# design.net
KiCad netlist of a schematic drawn in EasyEDA Pro
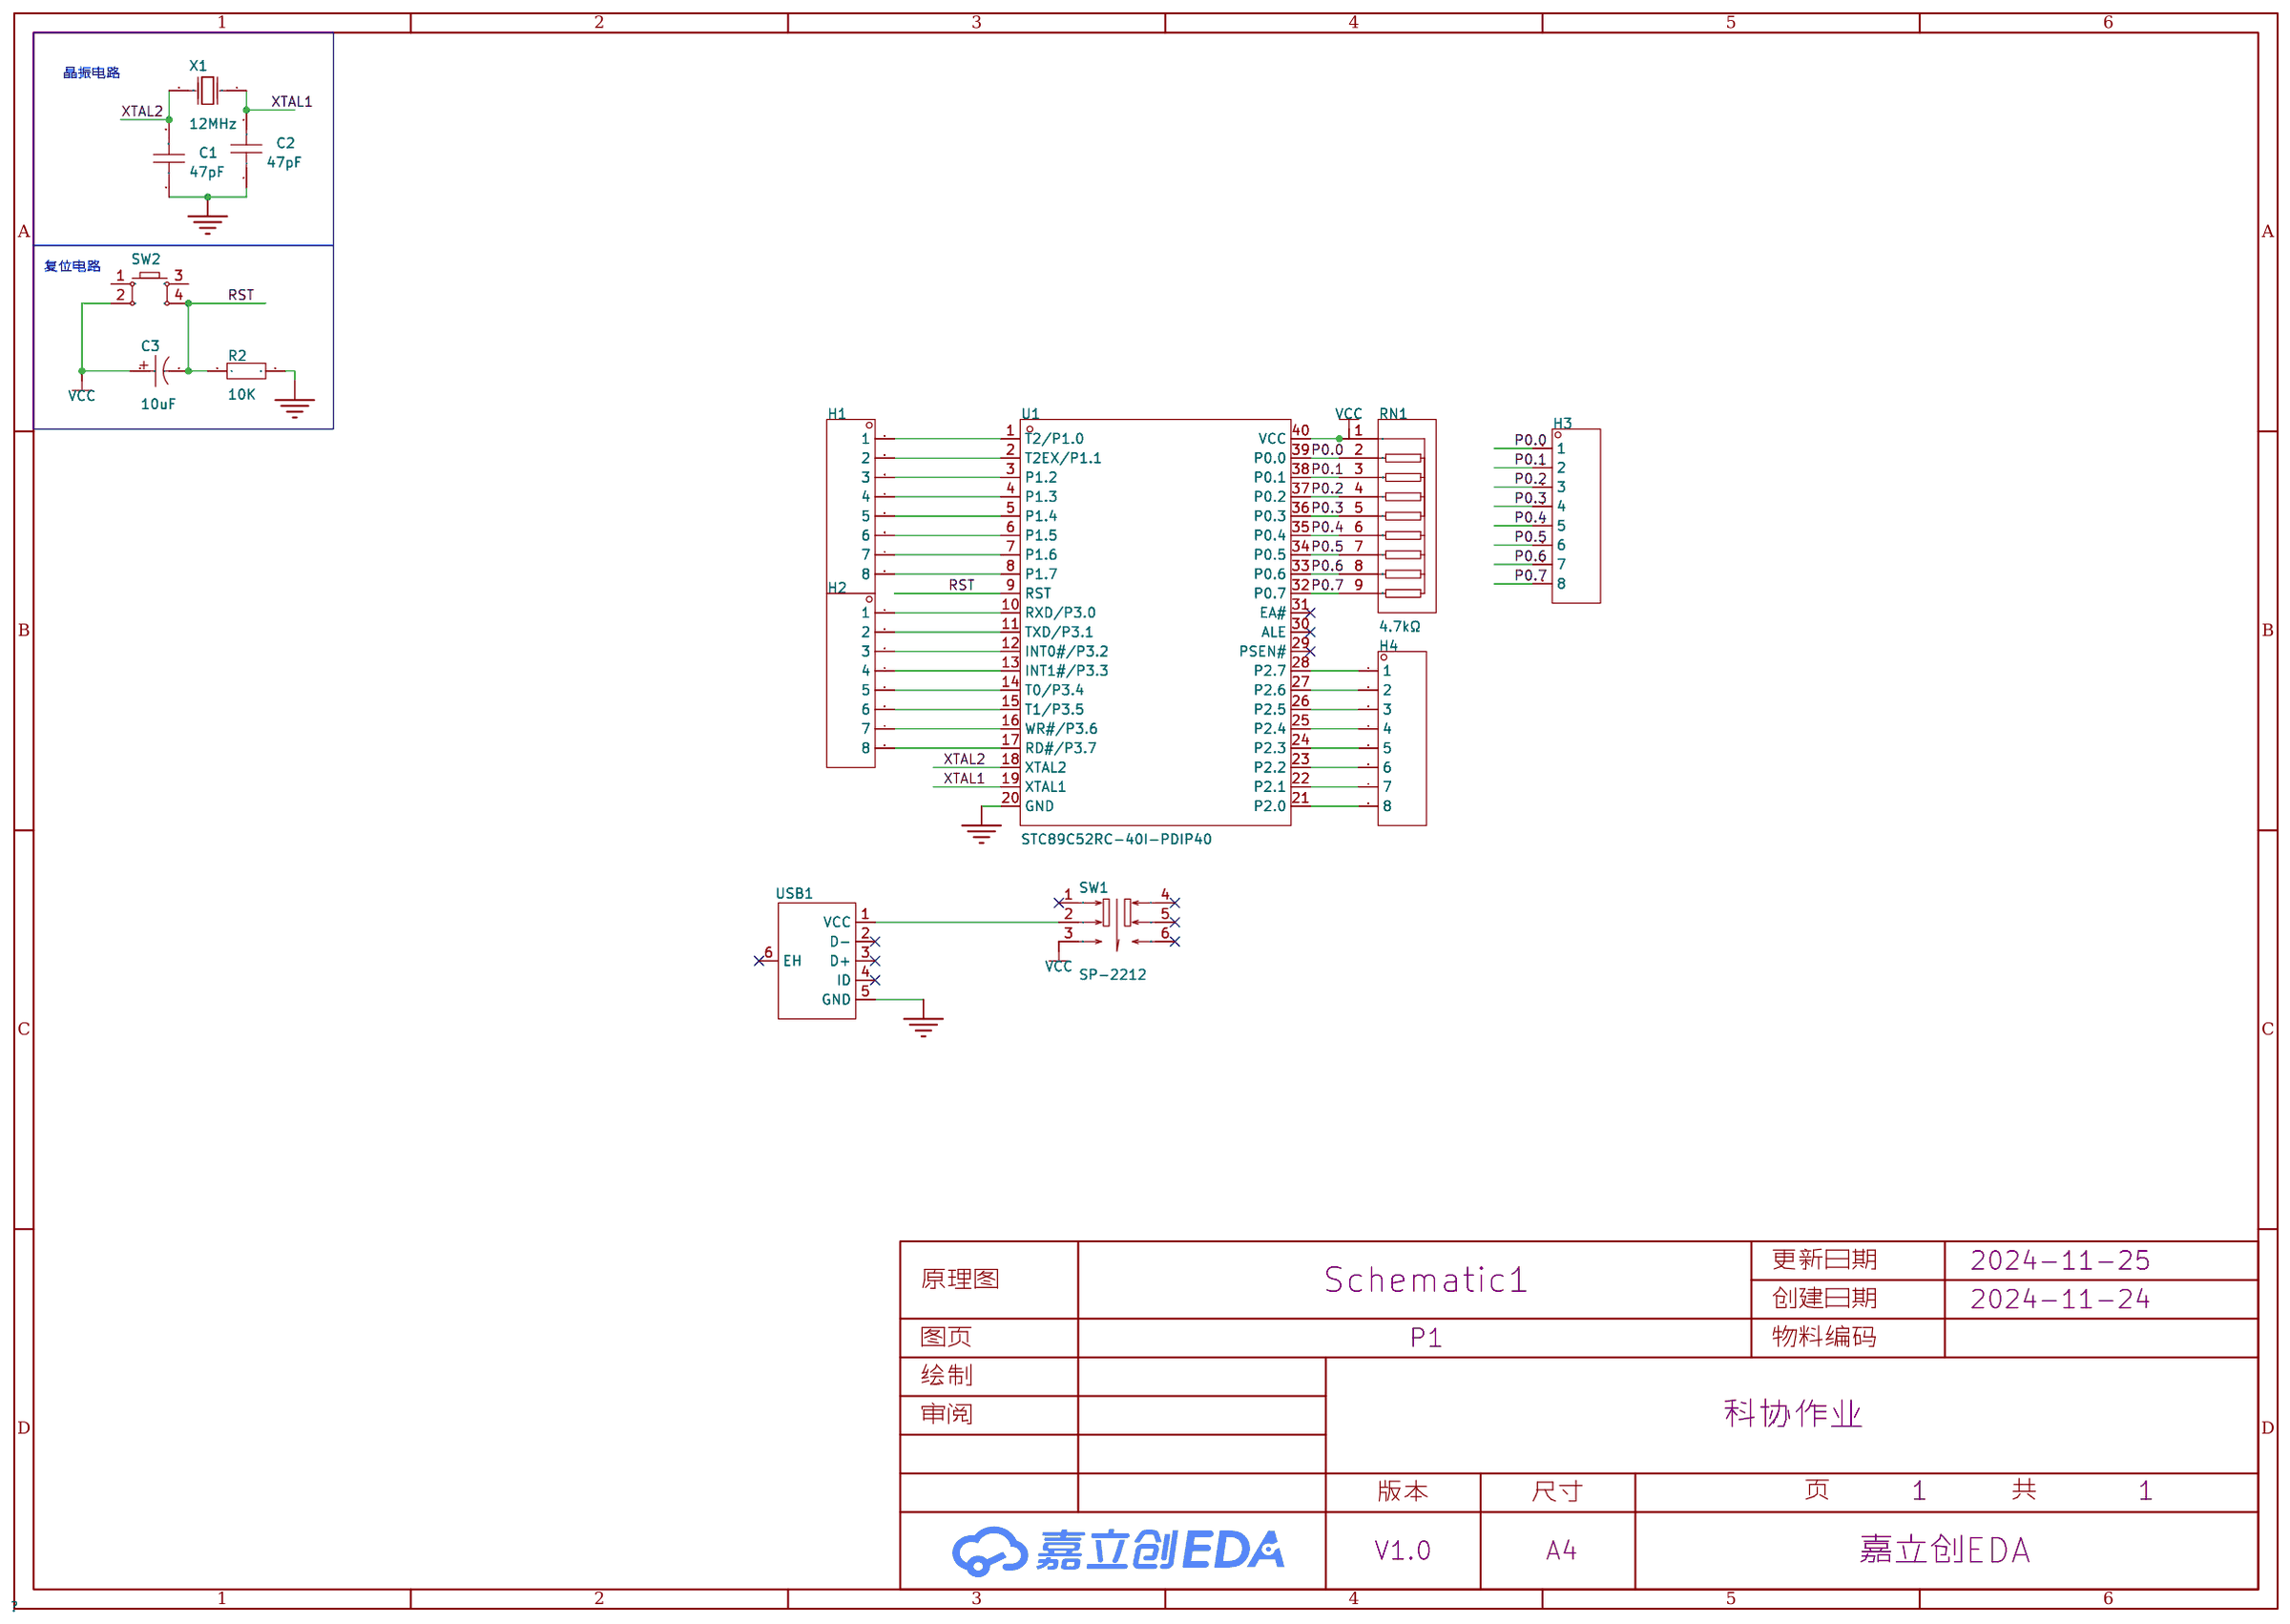
[diagram p0: schematic sheet]

(export (version "E")
  (design (tool "Eeschema 10.0.6"))
  (components
    (comp (ref "C1")
      (value "47pF")
      (footprint "easyedapro:C0603")
      (libsource (lib "easyedapro") (part "CapAcitance"))
    )
    (comp (ref "C2")
      (value "47pF")
      (footprint "easyedapro:C0603")
      (libsource (lib "easyedapro") (part "CapAcitance"))
    )
    (comp (ref "C3")
      (value "10uF")
      (footprint "easyedapro:CAP-TH_BD10.0-P5.00-D1.0-FD")
      (description "容值:220uF;精度:±20%;额定电压:50V;")
      (fields (field (name "Manufacturer Part") "ERS1HM221G16OT") (field (name "Manufacturer") "AISHI(艾华集团)"))
      (libsource (lib "easyedapro") (part "ERS1HM221G16OT"))
    )
    (comp (ref "H1")
      (value "~")
      (footprint "easyedapro:HDR-TH_8P-P2.54-V-M")
      (libsource (lib "easyedapro") (part "Header-Male-2.54_1x8"))
    )
    (comp (ref "H2")
      (value "~")
      (footprint "easyedapro:HDR-TH_8P-P2.54-V-M")
      (libsource (lib "easyedapro") (part "Header-Male-2.54_1x8"))
    )
    (comp (ref "H3")
      (value "~")
      (footprint "easyedapro:HDR-TH_8P-P2.54-V-M")
      (libsource (lib "easyedapro") (part "Header-Male-2.54_1x8"))
    )
    (comp (ref "H4")
      (value "~")
      (footprint "easyedapro:HDR-TH_8P-P2.54-V-M")
      (libsource (lib "easyedapro") (part "Header-Male-2.54_1x8"))
    )
    (comp (ref "R2") (value "10K") (footprint "easyedapro:R2010") (libsource (lib "easyedapro") (part "电阻")))
    (comp (ref "RN1")
      (value "4.7kΩ")
      (footprint "easyedapro:RES-ARRAY-TH_9P-P2.54-D1.0")
      (description "电阻器数:8;阻值:4.7kΩ;精度:±5%;单个元件功率:125mW;温度系数:±100ppm/°C;")
      (fields (field (name "Manufacturer Part") "A09-472JP") (field (name "Manufacturer") "FH(风华)"))
      (libsource (lib "easyedapro") (part "A09-472JP"))
    )
    (comp (ref "SW1")
      (value "SP-2212")
      (footprint "easyedapro:SW-TH_6P-L7.2-W7.2-P2.00-LS5.0")
      (description "电路结构:双刀双掷;自锁/无锁:自锁;安装方式:直插;触点电流:100mA;额定电压 (DC):30V;作用力:230gf;机械寿命:1.2万次;")
      (fields (field (name "Manufacturer") "RISHENG(日昇)"))
      (libsource (lib "easyedapro") (part "SP-2212"))
    )
    (comp (ref "SW2")
      (value "~")
      (footprint "easyedapro:Key_SMD_12x12x7.3")
      (libsource (lib "easyedapro") (part "轻触按键"))
    )
    (comp (ref "U1")
      (value "STC89C52RC-40I-PDIP40")
      (footprint "easyedapro:DIP-40_L52.0-W13.7-P2.54-LS15.2-BL")
      (description "CPU内核:51系列;程序存储容量:8KB;RAM总容量:512Byte;GPIO端口数量:35;工作电压范围:3.3V~5.5V;CPU最大主频:-;程序存储器类型:FLASH;")
      (fields (field (name "Manufacturer") "STC(宏晶)"))
      (libsource (lib "easyedapro") (part "STC89C52RC-40I"))
    )
    (comp (ref "USB1")
      (value "~")
      (footprint "easyedapro:USB_Micro")
      (libsource (lib "easyedapro") (part "USB_Micro"))
    )
    (comp (ref "X1")
      (value "12MHz")
      (footprint "easyedapro:HC-49US_L11.5-W4.5-P4.88")
      (description "晶振类型:直插晶振;频率:13MHz;常温频差:±20ppm;外接负载电容:20pF;频率稳定度(全温):±30ppm;")
      (fields (field (name "Manufacturer Part") "X49SD13MSD2SC") (field (name "Manufacturer") "YXC(扬兴晶振)"))
      (libsource (lib "easyedapro") (part "X49SD13MSD2SC"))
    )
  )
  (nets
    (net (code "1") (name "/P0.0") (class "Default")
      (node (ref "H3") (pin "1") (pinfunction "1_1") (pintype "unspecified"))
      (node (ref "RN1") (pin "2") (pinfunction "2_2") (pintype "unspecified"))
      (node (ref "U1") (pin "39") (pinfunction "P0.0_39") (pintype "unspecified"))
    )
    (net (code "2") (name "/P0.1") (class "Default")
      (node (ref "H3") (pin "2") (pinfunction "2_2") (pintype "unspecified"))
      (node (ref "RN1") (pin "3") (pinfunction "3_3") (pintype "unspecified"))
      (node (ref "U1") (pin "38") (pinfunction "P0.1_38") (pintype "unspecified"))
    )
    (net (code "3") (name "/P0.2") (class "Default")
      (node (ref "H3") (pin "3") (pinfunction "3_3") (pintype "unspecified"))
      (node (ref "RN1") (pin "4") (pinfunction "4_4") (pintype "unspecified"))
      (node (ref "U1") (pin "37") (pinfunction "P0.2_37") (pintype "unspecified"))
    )
    (net (code "4") (name "/P0.3") (class "Default")
      (node (ref "H3") (pin "4") (pinfunction "4_4") (pintype "unspecified"))
      (node (ref "RN1") (pin "5") (pinfunction "5_5") (pintype "unspecified"))
      (node (ref "U1") (pin "36") (pinfunction "P0.3_36") (pintype "unspecified"))
    )
    (net (code "5") (name "/P0.4") (class "Default")
      (node (ref "H3") (pin "5") (pinfunction "5_5") (pintype "unspecified"))
      (node (ref "RN1") (pin "6") (pinfunction "6_6") (pintype "unspecified"))
      (node (ref "U1") (pin "35") (pinfunction "P0.4_35") (pintype "unspecified"))
    )
    (net (code "6") (name "/P0.5") (class "Default")
      (node (ref "H3") (pin "6") (pinfunction "6_6") (pintype "unspecified"))
      (node (ref "RN1") (pin "7") (pinfunction "7_7") (pintype "unspecified"))
      (node (ref "U1") (pin "34") (pinfunction "P0.5_34") (pintype "unspecified"))
    )
    (net (code "7") (name "/P0.6") (class "Default")
      (node (ref "H3") (pin "7") (pinfunction "7_7") (pintype "unspecified"))
      (node (ref "RN1") (pin "8") (pinfunction "8_8") (pintype "unspecified"))
      (node (ref "U1") (pin "33") (pinfunction "P0.6_33") (pintype "unspecified"))
    )
    (net (code "8") (name "/P0.7") (class "Default")
      (node (ref "H3") (pin "8") (pinfunction "8_8") (pintype "unspecified"))
      (node (ref "RN1") (pin "9") (pinfunction "9_9") (pintype "unspecified"))
      (node (ref "U1") (pin "32") (pinfunction "P0.7_32") (pintype "unspecified"))
    )
    (net (code "9") (name "/RST") (class "Default")
      (node (ref "C3") (pin "2") (pinfunction "2_2") (pintype "input"))
      (node (ref "R2") (pin "1") (pinfunction "1_1") (pintype "input"))
      (node (ref "SW2") (pin "4") (pinfunction "4_4") (pintype "input"))
      (node (ref "U1") (pin "9") (pinfunction "RST_9") (pintype "unspecified"))
    )
    (net (code "10") (name "/XTAL1") (class "Default")
      (node (ref "C2") (pin "2") (pinfunction "2_2") (pintype "input"))
      (node (ref "U1") (pin "19") (pinfunction "XTAL1_19") (pintype "unspecified"))
      (node (ref "X1") (pin "1") (pinfunction "OSC1_1") (pintype "input"))
    )
    (net (code "11") (name "/XTAL2") (class "Default")
      (node (ref "C1") (pin "2") (pinfunction "2_2") (pintype "input"))
      (node (ref "U1") (pin "18") (pinfunction "XTAL2_18") (pintype "unspecified"))
      (node (ref "X1") (pin "2") (pinfunction "OSC2_2") (pintype "input"))
    )
    (net (code "12") (name "GND") (class "Default")
      (node (ref "C1") (pin "1") (pinfunction "1_1") (pintype "input"))
      (node (ref "C2") (pin "1") (pinfunction "1_1") (pintype "input"))
      (node (ref "R2") (pin "2") (pinfunction "2_2") (pintype "input"))
      (node (ref "U1") (pin "20") (pinfunction "GND_20") (pintype "unspecified"))
      (node (ref "USB1") (pin "5") (pinfunction "GND_5") (pintype "input"))
    )
    (net (code "13") (name "Net-(U1-INT0#{slash}P3.2)") (class "Default")
      (node (ref "H2") (pin "3") (pinfunction "3_3") (pintype "unspecified"))
      (node (ref "U1") (pin "12") (pinfunction "INT0#/P3.2_12") (pintype "unspecified"))
    )
    (net (code "14") (name "Net-(U1-INT1#{slash}P3.3)") (class "Default")
      (node (ref "H2") (pin "4") (pinfunction "4_4") (pintype "unspecified"))
      (node (ref "U1") (pin "13") (pinfunction "INT1#/P3.3_13") (pintype "unspecified"))
    )
    (net (code "15") (name "Net-(U1-P1.2)") (class "Default")
      (node (ref "H1") (pin "3") (pinfunction "3_3") (pintype "unspecified"))
      (node (ref "U1") (pin "3") (pinfunction "P1.2_3") (pintype "unspecified"))
    )
    (net (code "16") (name "Net-(U1-P1.3)") (class "Default")
      (node (ref "H1") (pin "4") (pinfunction "4_4") (pintype "unspecified"))
      (node (ref "U1") (pin "4") (pinfunction "P1.3_4") (pintype "unspecified"))
    )
    (net (code "17") (name "Net-(U1-P1.4)") (class "Default")
      (node (ref "H1") (pin "5") (pinfunction "5_5") (pintype "unspecified"))
      (node (ref "U1") (pin "5") (pinfunction "P1.4_5") (pintype "unspecified"))
    )
    (net (code "18") (name "Net-(U1-P1.5)") (class "Default")
      (node (ref "H1") (pin "6") (pinfunction "6_6") (pintype "unspecified"))
      (node (ref "U1") (pin "6") (pinfunction "P1.5_6") (pintype "unspecified"))
    )
    (net (code "19") (name "Net-(U1-P1.6)") (class "Default")
      (node (ref "H1") (pin "7") (pinfunction "7_7") (pintype "unspecified"))
      (node (ref "U1") (pin "7") (pinfunction "P1.6_7") (pintype "unspecified"))
    )
    (net (code "20") (name "Net-(U1-P1.7)") (class "Default")
      (node (ref "H1") (pin "8") (pinfunction "8_8") (pintype "unspecified"))
      (node (ref "U1") (pin "8") (pinfunction "P1.7_8") (pintype "unspecified"))
    )
    (net (code "21") (name "Net-(U1-P2.0)") (class "Default")
      (node (ref "H4") (pin "8") (pinfunction "8_8") (pintype "unspecified"))
      (node (ref "U1") (pin "21") (pinfunction "P2.0_21") (pintype "unspecified"))
    )
    (net (code "22") (name "Net-(U1-P2.1)") (class "Default")
      (node (ref "H4") (pin "7") (pinfunction "7_7") (pintype "unspecified"))
      (node (ref "U1") (pin "22") (pinfunction "P2.1_22") (pintype "unspecified"))
    )
    (net (code "23") (name "Net-(U1-P2.2)") (class "Default")
      (node (ref "H4") (pin "6") (pinfunction "6_6") (pintype "unspecified"))
      (node (ref "U1") (pin "23") (pinfunction "P2.2_23") (pintype "unspecified"))
    )
    (net (code "24") (name "Net-(U1-P2.3)") (class "Default")
      (node (ref "H4") (pin "5") (pinfunction "5_5") (pintype "unspecified"))
      (node (ref "U1") (pin "24") (pinfunction "P2.3_24") (pintype "unspecified"))
    )
    (net (code "25") (name "Net-(U1-P2.4)") (class "Default")
      (node (ref "H4") (pin "4") (pinfunction "4_4") (pintype "unspecified"))
      (node (ref "U1") (pin "25") (pinfunction "P2.4_25") (pintype "unspecified"))
    )
    (net (code "26") (name "Net-(U1-P2.5)") (class "Default")
      (node (ref "H4") (pin "3") (pinfunction "3_3") (pintype "unspecified"))
      (node (ref "U1") (pin "26") (pinfunction "P2.5_26") (pintype "unspecified"))
    )
    (net (code "27") (name "Net-(U1-P2.6)") (class "Default")
      (node (ref "H4") (pin "2") (pinfunction "2_2") (pintype "unspecified"))
      (node (ref "U1") (pin "27") (pinfunction "P2.6_27") (pintype "unspecified"))
    )
    (net (code "28") (name "Net-(U1-P2.7)") (class "Default")
      (node (ref "H4") (pin "1") (pinfunction "1_1") (pintype "unspecified"))
      (node (ref "U1") (pin "28") (pinfunction "P2.7_28") (pintype "unspecified"))
    )
    (net (code "29") (name "Net-(U1-RD#{slash}P3.7)") (class "Default")
      (node (ref "H2") (pin "8") (pinfunction "8_8") (pintype "unspecified"))
      (node (ref "U1") (pin "17") (pinfunction "RD#/P3.7_17") (pintype "unspecified"))
    )
    (net (code "30") (name "Net-(U1-RXD{slash}P3.0)") (class "Default")
      (node (ref "H2") (pin "1") (pinfunction "1_1") (pintype "unspecified"))
      (node (ref "U1") (pin "10") (pinfunction "RXD/P3.0_10") (pintype "unspecified"))
    )
    (net (code "31") (name "Net-(U1-T0{slash}P3.4)") (class "Default")
      (node (ref "H2") (pin "5") (pinfunction "5_5") (pintype "unspecified"))
      (node (ref "U1") (pin "14") (pinfunction "T0/P3.4_14") (pintype "unspecified"))
    )
    (net (code "32") (name "Net-(U1-T1{slash}P3.5)") (class "Default")
      (node (ref "H2") (pin "6") (pinfunction "6_6") (pintype "unspecified"))
      (node (ref "U1") (pin "15") (pinfunction "T1/P3.5_15") (pintype "unspecified"))
    )
    (net (code "33") (name "Net-(U1-T2EX{slash}P1.1)") (class "Default")
      (node (ref "H1") (pin "2") (pinfunction "2_2") (pintype "unspecified"))
      (node (ref "U1") (pin "2") (pinfunction "T2EX/P1.1_2") (pintype "unspecified"))
    )
    (net (code "34") (name "Net-(U1-T2{slash}P1.0)") (class "Default")
      (node (ref "H1") (pin "1") (pinfunction "1_1") (pintype "unspecified"))
      (node (ref "U1") (pin "1") (pinfunction "T2/P1.0_1") (pintype "unspecified"))
    )
    (net (code "35") (name "Net-(U1-TXD{slash}P3.1)") (class "Default")
      (node (ref "H2") (pin "2") (pinfunction "2_2") (pintype "unspecified"))
      (node (ref "U1") (pin "11") (pinfunction "TXD/P3.1_11") (pintype "unspecified"))
    )
    (net (code "36") (name "Net-(U1-WR#{slash}P3.6)") (class "Default")
      (node (ref "H2") (pin "7") (pinfunction "7_7") (pintype "unspecified"))
      (node (ref "U1") (pin "16") (pinfunction "WR#/P3.6_16") (pintype "unspecified"))
    )
    (net (code "37") (name "Net-(USB1-VCC)") (class "Default")
      (node (ref "SW1") (pin "2") (pinfunction "2_2") (pintype "unspecified"))
      (node (ref "USB1") (pin "1") (pinfunction "VCC_1") (pintype "input"))
    )
    (net (code "38") (name "VCC") (class "Default")
      (node (ref "C3") (pin "1") (pinfunction "1_1") (pintype "input"))
      (node (ref "RN1") (pin "1") (pinfunction "1_1") (pintype "unspecified"))
      (node (ref "SW1") (pin "3") (pinfunction "3_3") (pintype "unspecified"))
      (node (ref "SW2") (pin "2") (pinfunction "2_2") (pintype "input"))
      (node (ref "U1") (pin "40") (pinfunction "VCC_40") (pintype "unspecified"))
    )
    (net (code "39") (name "unconnected-(SW1-Pad1)") (class "Default")
      (node (ref "SW1") (pin "1") (pinfunction "1_1") (pintype "unspecified+no_connect"))
    )
    (net (code "40") (name "unconnected-(SW1-Pad4)") (class "Default")
      (node (ref "SW1") (pin "4") (pinfunction "4_4") (pintype "unspecified+no_connect"))
    )
    (net (code "41") (name "unconnected-(SW1-Pad5)") (class "Default")
      (node (ref "SW1") (pin "5") (pinfunction "5_5") (pintype "unspecified+no_connect"))
    )
    (net (code "42") (name "unconnected-(SW1-Pad6)") (class "Default")
      (node (ref "SW1") (pin "6") (pinfunction "6_6") (pintype "unspecified+no_connect"))
    )
    (net (code "43") (name "unconnected-(SW2-Pad1)") (class "Default")
      (node (ref "SW2") (pin "1") (pinfunction "1_1") (pintype "input"))
    )
    (net (code "44") (name "unconnected-(SW2-Pad3)") (class "Default")
      (node (ref "SW2") (pin "3") (pinfunction "3_3") (pintype "input"))
    )
    (net (code "45") (name "unconnected-(U1-ALE-Pad30)") (class "Default")
      (node (ref "U1") (pin "30") (pinfunction "ALE_30") (pintype "unspecified+no_connect"))
    )
    (net (code "46") (name "unconnected-(U1-EA#-Pad31)") (class "Default")
      (node (ref "U1") (pin "31") (pinfunction "EA#_31") (pintype "unspecified+no_connect"))
    )
    (net (code "47") (name "unconnected-(U1-PSEN#-Pad29)") (class "Default")
      (node (ref "U1") (pin "29") (pinfunction "PSEN#_29") (pintype "unspecified+no_connect"))
    )
    (net (code "48") (name "unconnected-(USB1-D+-Pad3)") (class "Default")
      (node (ref "USB1") (pin "3") (pinfunction "D+_3") (pintype "input+no_connect"))
    )
    (net (code "49") (name "unconnected-(USB1-D--Pad2)") (class "Default")
      (node (ref "USB1") (pin "2") (pinfunction "D-_2") (pintype "input+no_connect"))
    )
    (net (code "50") (name "unconnected-(USB1-EH-Pad6)") (class "Default")
      (node (ref "USB1") (pin "6") (pinfunction "EH_6") (pintype "input+no_connect"))
    )
    (net (code "51") (name "unconnected-(USB1-ID-Pad4)") (class "Default")
      (node (ref "USB1") (pin "4") (pinfunction "ID_4") (pintype "input+no_connect"))
    )
  )
)
